# Sheet1.net
KiCad netlist of a schematic drawn in Altium Designer
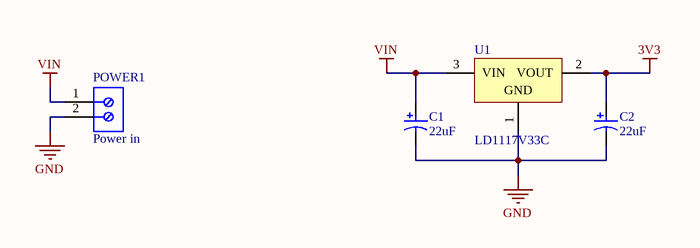
[diagram p0: Sheet1.SchDoc]

(export (version "E")
  (design (tool "Eeschema 10.0.6"))
  (components
    (comp (ref "C1")
      (value "22uF")
      (footprint "CAPPR55-200-1100X500X1200")
      (description "Aluminum Electrolytic Capacitor, 22 uF, +/- 20%, 50 V, -40 to 85 degC, 2-Pin THD, RoHS, Bulk")
      (fields (field (name "VOLTAGE") "50V") (field (name "MANUFACTURER") "Panasonic"))
      (libsource (lib "Altium Content Vault") (part "CAP-P-2"))
    )
    (comp (ref "C2")
      (value "22uF")
      (footprint "CAPPR55-200-1100X500X1200")
      (description "Aluminum Electrolytic Capacitor, 22 uF, +/- 20%, 50 V, -40 to 85 degC, 2-Pin THD, RoHS, Bulk")
      (fields (field (name "VOLTAGE") "50V") (field (name "MANUFACTURER") "Panasonic"))
      (libsource (lib "Altium Content Vault") (part "CAP-P-2"))
    )
    (comp (ref "POWER1")
      (value "Power in")
      (footprint "691102710002")
      (description "Series 102 - 5.00 mm Horizontal Entry Modular with Pressure Clamp WR-TBL, 2 pin")
      (fields
        (field (name "MANUFACTURER") "Wurth Elektronik")
        (field (name "PART NUMBER") "691102710002")
        (field (name "PUBLISHER") "WurthElektronik")
      )
      (libsource (lib "Altium Content Vault") (part "WE-CN-1P-F-TB2"))
    )
    (comp (ref "U1")
      (value "LD1117V33C")
      (footprint "TO220")
      (description "Fixed Low Drop Positive Voltage Regulator, 3.3V, 3-Pin TO-220")
      (libsource (lib "Altium Content Vault") (part "PM-REG-LD1117V-SIL3"))
    )
  )
  (nets
    (net (code "1") (name "3V3") (class "Default")
      (node (ref "C2") (pin "1") (pinfunction "1_1") (pintype "passive"))
      (node (ref "U1") (pin "2") (pinfunction "VOUT_2") (pintype "power_in"))
    )
    (net (code "2") (name "GND") (class "Default")
      (node (ref "C1") (pin "2") (pinfunction "2_2") (pintype "passive"))
      (node (ref "C2") (pin "2") (pinfunction "2_2") (pintype "passive"))
      (node (ref "POWER1") (pin "2") (pinfunction "2_2") (pintype "passive"))
      (node (ref "U1") (pin "1") (pinfunction "GND_1") (pintype "power_in"))
    )
    (net (code "3") (name "VIN") (class "Default")
      (node (ref "C1") (pin "1") (pinfunction "1_1") (pintype "passive"))
      (node (ref "POWER1") (pin "1") (pinfunction "1_1") (pintype "passive"))
      (node (ref "U1") (pin "3") (pinfunction "VIN_3") (pintype "power_in"))
    )
  )
)
